# pcb-bldc-drive.net
KiCad netlist of a schematic drawn in EAGLE
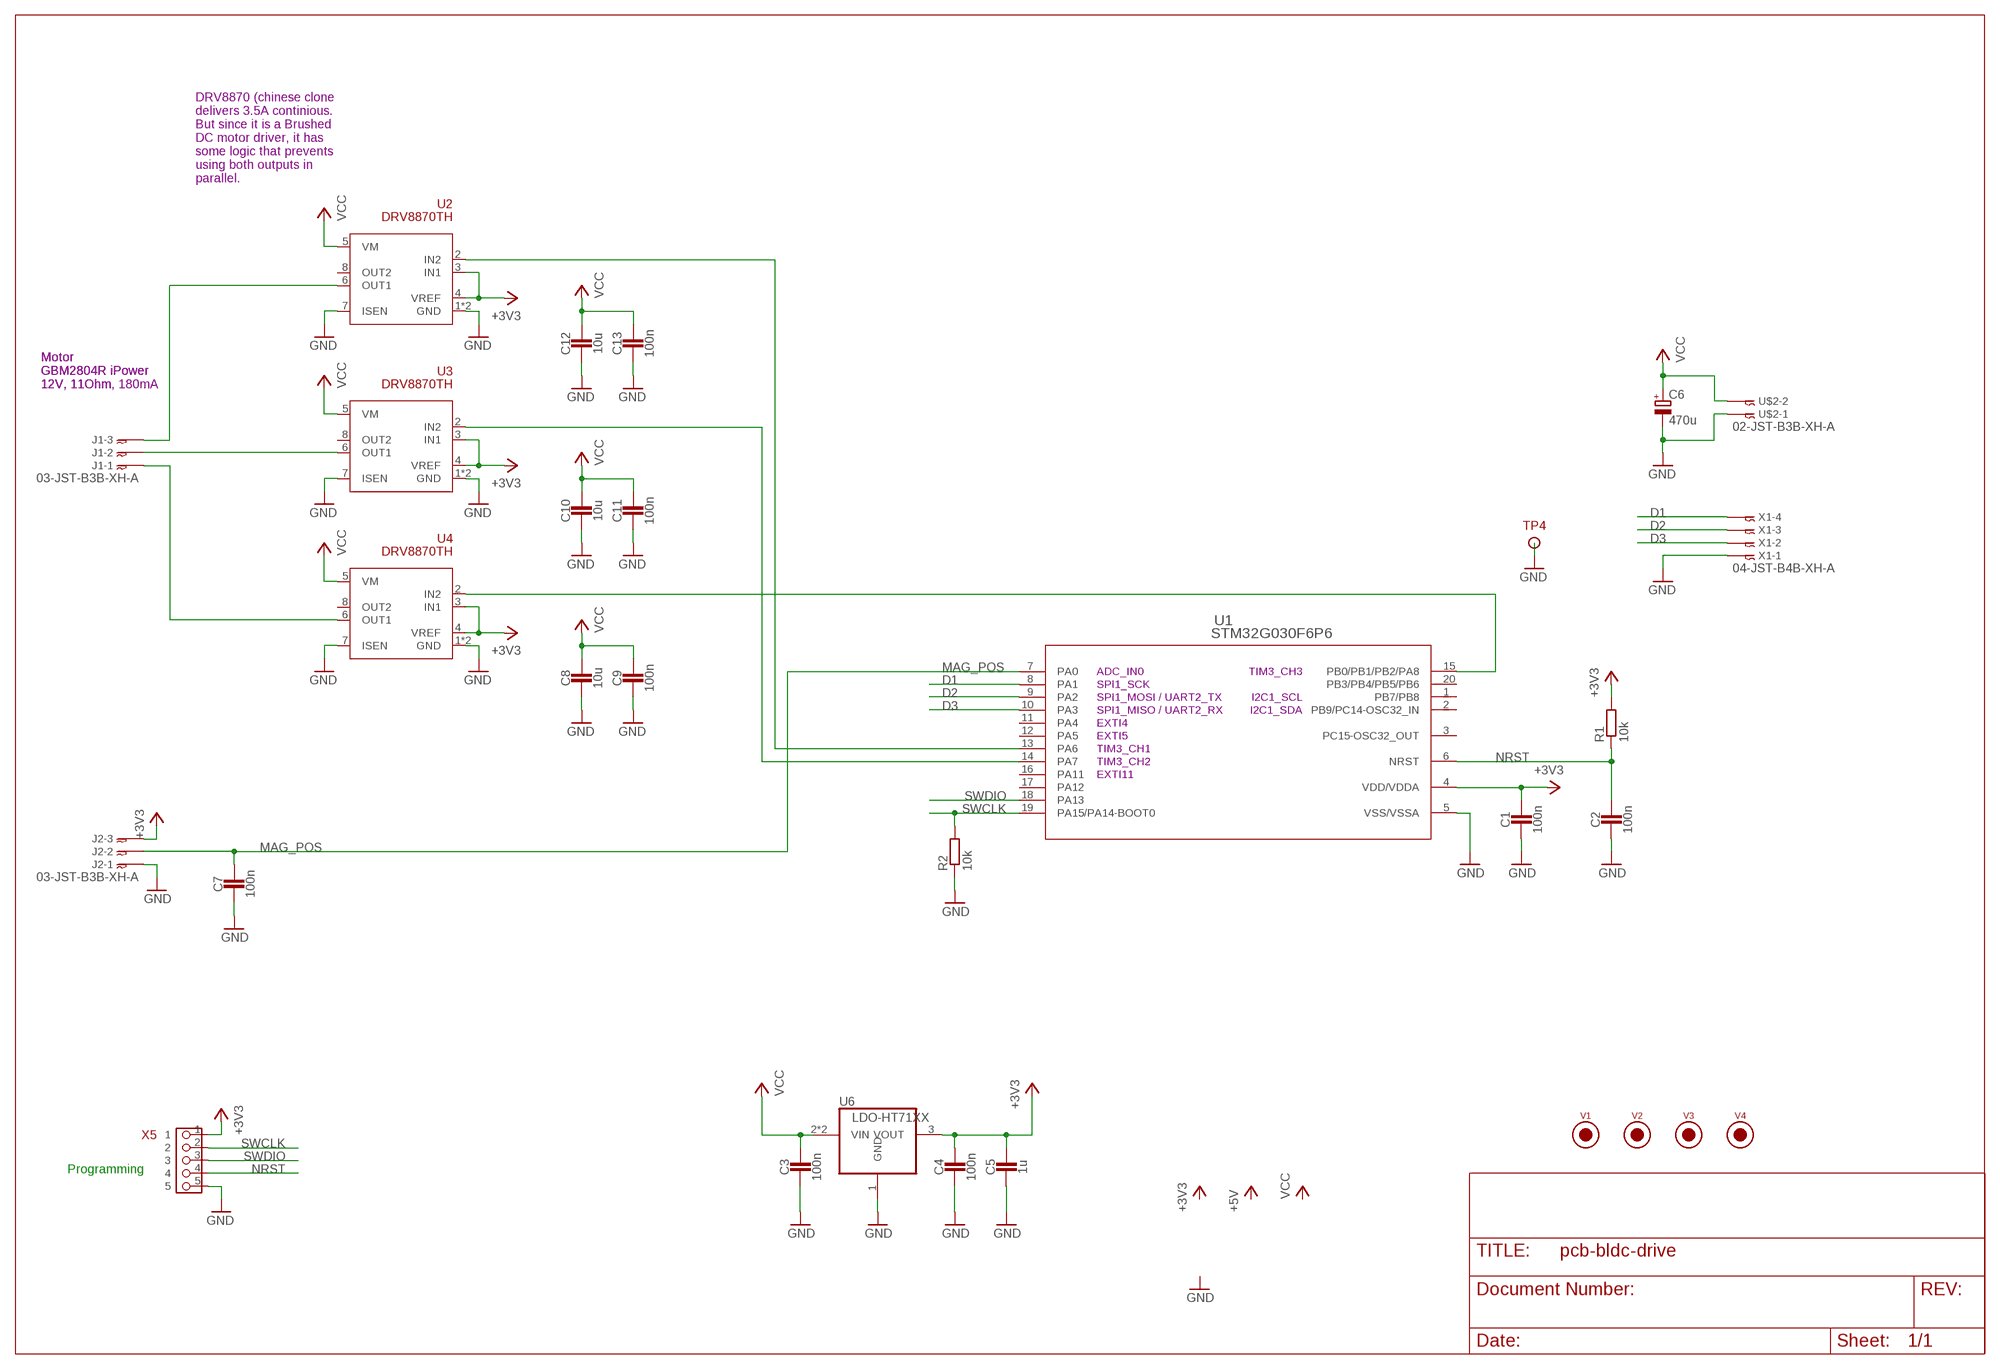
[diagram p0: schematic, sheet 1]

(export (version "E")
  (design (tool "Eeschema 10.0.6"))
  (components
    (comp (ref "C1")
      (value "100n")
      (footprint "eagle-import:0603_CAP")
      (libsource (lib "eagle-import") (part "CAPACITOR0603_CAP"))
    )
    (comp (ref "C2")
      (value "100n")
      (footprint "eagle-import:0603_CAP")
      (libsource (lib "eagle-import") (part "CAPACITOR0603_CAP"))
    )
    (comp (ref "C3")
      (value "100n")
      (footprint "eagle-import:0603_CAP")
      (libsource (lib "eagle-import") (part "CAPACITOR0603_CAP"))
    )
    (comp (ref "C4")
      (value "100n")
      (footprint "eagle-import:0603_CAP")
      (libsource (lib "eagle-import") (part "CAPACITOR0603_CAP"))
    )
    (comp (ref "C5")
      (value "1u")
      (footprint "eagle-import:0603_CAP")
      (libsource (lib "eagle-import") (part "CAPACITOR0603_CAP"))
    )
    (comp (ref "C6")
      (value "470u")
      (footprint "eagle-import:153CLV-1010")
      (libsource (lib "eagle-import") (part "CPOL-EU153CLV-1010"))
    )
    (comp (ref "C7")
      (value "100n")
      (footprint "eagle-import:0603_CAP")
      (libsource (lib "eagle-import") (part "CAPACITOR0603_CAP"))
    )
    (comp (ref "C8")
      (value "10u")
      (footprint "eagle-import:1206_CAP")
      (libsource (lib "eagle-import") (part "CAPACITOR1206_CAP"))
    )
    (comp (ref "C9")
      (value "100n")
      (footprint "eagle-import:0603_CAP")
      (libsource (lib "eagle-import") (part "CAPACITOR0603_CAP"))
    )
    (comp (ref "C10")
      (value "10u")
      (footprint "eagle-import:1206_CAP")
      (libsource (lib "eagle-import") (part "CAPACITOR1206_CAP"))
    )
    (comp (ref "C11")
      (value "100n")
      (footprint "eagle-import:0603_CAP")
      (libsource (lib "eagle-import") (part "CAPACITOR0603_CAP"))
    )
    (comp (ref "C12")
      (value "10u")
      (footprint "eagle-import:1206_CAP")
      (libsource (lib "eagle-import") (part "CAPACITOR1206_CAP"))
    )
    (comp (ref "C13")
      (value "100n")
      (footprint "eagle-import:0603_CAP")
      (libsource (lib "eagle-import") (part "CAPACITOR0603_CAP"))
    )
    (comp (ref "J1")
      (value "03-JST-B3B-XH-A")
      (footprint "eagle-import:B3B-XH")
      (libsource (lib "eagle-import") (part "03-JST-B3B-XH-A"))
    )
    (comp (ref "J2")
      (value "03-JST-B3B-XH-A")
      (footprint "eagle-import:B3B-XH")
      (libsource (lib "eagle-import") (part "03-JST-B3B-XH-A"))
    )
    (comp (ref "R1")
      (value "10k")
      (footprint "eagle-import:0603-RES")
      (libsource (lib "eagle-import") (part "RESISTOR0603_RES"))
    )
    (comp (ref "R2")
      (value "10k")
      (footprint "eagle-import:0603-RES")
      (libsource (lib "eagle-import") (part "RESISTOR0603_RES"))
    )
    (comp (ref "TP4")
      (value "TESTPIN1MM")
      (footprint "eagle-import:PIN-SMD-1X1-TEST_1M0")
      (libsource (lib "eagle-import") (part "TESTPIN1MM"))
    )
    (comp (ref "U$2")
      (value "02-JST-B3B-XH-A")
      (footprint "eagle-import:B2B-XH")
      (libsource (lib "eagle-import") (part "02-JST-B3B-XH-A"))
    )
    (comp (ref "U1")
      (value "STM32G030F6P6")
      (footprint "eagle-import:TSSOP20")
      (fields (field (name "COPYRIGHT") "Copyright (C) 2024 Ultra Librarian. All rights reserved."))
      (libsource (lib "eagle-import") (part "STM32G030F6P6"))
    )
    (comp (ref "U2")
      (value "DRV8870TH")
      (footprint "eagle-import:SOIC-8-THERM")
      (libsource (lib "eagle-import") (part "DRV8870TH"))
    )
    (comp (ref "U3")
      (value "DRV8870TH")
      (footprint "eagle-import:SOIC-8-THERM")
      (libsource (lib "eagle-import") (part "DRV8870TH"))
    )
    (comp (ref "U4")
      (value "DRV8870TH")
      (footprint "eagle-import:SOIC-8-THERM")
      (libsource (lib "eagle-import") (part "DRV8870TH"))
    )
    (comp (ref "U6")
      (value "LDO-HT71XX")
      (footprint "eagle-import:SOT-89")
      (libsource (lib "eagle-import") (part "LDO-HT71XX"))
    )
    (comp (ref "V1")
      (value "FIDUCIAL2MM")
      (footprint "eagle-import:FIDUCIAL_2MM")
      (libsource (lib "eagle-import") (part "FIDUCIAL2MM"))
    )
    (comp (ref "V2")
      (value "FIDUCIAL2MM")
      (footprint "eagle-import:FIDUCIAL_2MM")
      (libsource (lib "eagle-import") (part "FIDUCIAL2MM"))
    )
    (comp (ref "V3")
      (value "FIDUCIAL2MM")
      (footprint "eagle-import:FIDUCIAL_2MM")
      (libsource (lib "eagle-import") (part "FIDUCIAL2MM"))
    )
    (comp (ref "V4")
      (value "FIDUCIAL2MM")
      (footprint "eagle-import:FIDUCIAL_2MM")
      (libsource (lib "eagle-import") (part "FIDUCIAL2MM"))
    )
    (comp (ref "X1")
      (value "04-JST-B4B-XH-A")
      (footprint "eagle-import:B4B-XH")
      (libsource (lib "eagle-import") (part "04-JST-B4B-XH-A"))
    )
    (comp (ref "X5")
      (value "PIN_5X1HD")
      (footprint "eagle-import:PIN_5X1_HD")
      (libsource (lib "eagle-import") (part "PIN_5X1HD"))
    )
  )
  (nets
    (net (code "1") (name "+3V3") (class "Default")
      (node (ref "C1") (pin "1") (pinfunction "1_1") (pintype "bidirectional"))
      (node (ref "C4") (pin "1") (pinfunction "1_1") (pintype "bidirectional"))
      (node (ref "C5") (pin "1") (pinfunction "1_1") (pintype "bidirectional"))
      (node (ref "J2") (pin "P$3") (pinfunction "1_P$3") (pintype "passive"))
      (node (ref "R1") (pin "2") (pinfunction "2_2") (pintype "passive"))
      (node (ref "U1") (pin "4") (pinfunction "VDD/VDDA_4") (pintype "power_in"))
      (node (ref "U2") (pin "3") (pinfunction "IN1_3") (pintype "bidirectional"))
      (node (ref "U2") (pin "4") (pinfunction "VREF_4") (pintype "bidirectional"))
      (node (ref "U3") (pin "3") (pinfunction "IN1_3") (pintype "bidirectional"))
      (node (ref "U3") (pin "4") (pinfunction "VREF_4") (pintype "bidirectional"))
      (node (ref "U4") (pin "3") (pinfunction "IN1_3") (pintype "bidirectional"))
      (node (ref "U4") (pin "4") (pinfunction "VREF_4") (pintype "bidirectional"))
      (node (ref "U6") (pin "3") (pinfunction "VOUT_3") (pintype "output"))
      (node (ref "X5") (pin "1") (pinfunction "1_1") (pintype "bidirectional"))
    )
    (net (code "3") (name "/D1") (class "Default")
      (node (ref "U1") (pin "8") (pinfunction "PA1_8") (pintype "bidirectional"))
      (node (ref "X1") (pin "P$4") (pinfunction "1_P$4") (pintype "passive"))
    )
    (net (code "4") (name "/D2") (class "Default")
      (node (ref "U1") (pin "9") (pinfunction "PA2_9") (pintype "bidirectional"))
      (node (ref "X1") (pin "P$3") (pinfunction "1_P$3") (pintype "passive"))
    )
    (net (code "5") (name "/D3") (class "Default")
      (node (ref "U1") (pin "10") (pinfunction "PA3_10") (pintype "bidirectional"))
      (node (ref "X1") (pin "P$2") (pinfunction "1_P$2") (pintype "passive"))
    )
    (net (code "6") (name "/MAG_POS") (class "Default")
      (node (ref "C7") (pin "1") (pinfunction "1_1") (pintype "bidirectional"))
      (node (ref "J2") (pin "P$2") (pinfunction "1_P$2") (pintype "passive"))
      (node (ref "U1") (pin "7") (pinfunction "PA0_7") (pintype "bidirectional"))
    )
    (net (code "7") (name "/NRST") (class "Default")
      (node (ref "C2") (pin "1") (pinfunction "1_1") (pintype "bidirectional"))
      (node (ref "R1") (pin "1") (pinfunction "1_1") (pintype "passive"))
      (node (ref "U1") (pin "6") (pinfunction "NRST_6") (pintype "bidirectional"))
      (node (ref "X5") (pin "4") (pinfunction "4_4") (pintype "bidirectional"))
    )
    (net (code "8") (name "/SWCLK") (class "Default")
      (node (ref "R2") (pin "2") (pinfunction "2_2") (pintype "passive"))
      (node (ref "U1") (pin "19") (pinfunction "PA15/PA14-BOOT0_19") (pintype "bidirectional"))
      (node (ref "X5") (pin "2") (pinfunction "2_2") (pintype "bidirectional"))
    )
    (net (code "9") (name "/SWDIO") (class "Default")
      (node (ref "U1") (pin "18") (pinfunction "PA13_18") (pintype "bidirectional"))
      (node (ref "X5") (pin "3") (pinfunction "3_3") (pintype "bidirectional"))
    )
    (net (code "10") (name "GND") (class "Default")
      (node (ref "C1") (pin "2") (pinfunction "2_2") (pintype "bidirectional"))
      (node (ref "C10") (pin "2") (pinfunction "2_2") (pintype "bidirectional"))
      (node (ref "C11") (pin "2") (pinfunction "2_2") (pintype "bidirectional"))
      (node (ref "C12") (pin "2") (pinfunction "2_2") (pintype "bidirectional"))
      (node (ref "C13") (pin "2") (pinfunction "2_2") (pintype "bidirectional"))
      (node (ref "C2") (pin "2") (pinfunction "2_2") (pintype "bidirectional"))
      (node (ref "C3") (pin "2") (pinfunction "2_2") (pintype "bidirectional"))
      (node (ref "C4") (pin "2") (pinfunction "2_2") (pintype "bidirectional"))
      (node (ref "C5") (pin "2") (pinfunction "2_2") (pintype "bidirectional"))
      (node (ref "C6") (pin "-") (pinfunction "-_-") (pintype "passive"))
      (node (ref "C7") (pin "2") (pinfunction "2_2") (pintype "bidirectional"))
      (node (ref "C8") (pin "2") (pinfunction "2_2") (pintype "bidirectional"))
      (node (ref "C9") (pin "2") (pinfunction "2_2") (pintype "bidirectional"))
      (node (ref "J2") (pin "P$1") (pinfunction "1_P$1") (pintype "passive"))
      (node (ref "R2") (pin "1") (pinfunction "1_1") (pintype "passive"))
      (node (ref "TP4") (pin "1") (pinfunction "1_1") (pintype "bidirectional"))
      (node (ref "U$2") (pin "P$1") (pinfunction "1_P$1") (pintype "passive"))
      (node (ref "U1") (pin "5") (pinfunction "VSS/VSSA_5") (pintype "power_in"))
      (node (ref "U2") (pin "1") (pinfunction "GND_1") (pintype "bidirectional"))
      (node (ref "U2") (pin "7") (pinfunction "ISEN_7") (pintype "bidirectional"))
      (node (ref "U2") (pin "9") (pinfunction "GND_9") (pintype "bidirectional"))
      (node (ref "U3") (pin "1") (pinfunction "GND_1") (pintype "bidirectional"))
      (node (ref "U3") (pin "7") (pinfunction "ISEN_7") (pintype "bidirectional"))
      (node (ref "U3") (pin "9") (pinfunction "GND_9") (pintype "bidirectional"))
      (node (ref "U4") (pin "1") (pinfunction "GND_1") (pintype "bidirectional"))
      (node (ref "U4") (pin "7") (pinfunction "ISEN_7") (pintype "bidirectional"))
      (node (ref "U4") (pin "9") (pinfunction "GND_9") (pintype "bidirectional"))
      (node (ref "U6") (pin "1") (pinfunction "GND_1") (pintype "power_in"))
      (node (ref "X1") (pin "P$1") (pinfunction "1_P$1") (pintype "passive"))
      (node (ref "X5") (pin "5") (pinfunction "5_5") (pintype "bidirectional"))
    )
    (net (code "11") (name "Net-(J1A-1)") (class "Default")
      (node (ref "J1") (pin "P$1") (pinfunction "1_P$1") (pintype "passive"))
      (node (ref "U4") (pin "6") (pinfunction "OUT1_6") (pintype "bidirectional"))
    )
    (net (code "12") (name "Net-(J1B-1)") (class "Default")
      (node (ref "J1") (pin "P$2") (pinfunction "1_P$2") (pintype "passive"))
      (node (ref "U3") (pin "6") (pinfunction "OUT1_6") (pintype "bidirectional"))
    )
    (net (code "13") (name "Net-(J1C-1)") (class "Default")
      (node (ref "J1") (pin "P$3") (pinfunction "1_P$3") (pintype "passive"))
      (node (ref "U2") (pin "6") (pinfunction "OUT1_6") (pintype "bidirectional"))
    )
    (net (code "14") (name "Net-(U1-PA6)") (class "Default")
      (node (ref "U1") (pin "13") (pinfunction "PA6_13") (pintype "bidirectional"))
      (node (ref "U2") (pin "2") (pinfunction "IN2_2") (pintype "bidirectional"))
    )
    (net (code "15") (name "Net-(U1-PA7)") (class "Default")
      (node (ref "U1") (pin "14") (pinfunction "PA7_14") (pintype "bidirectional"))
      (node (ref "U3") (pin "2") (pinfunction "IN2_2") (pintype "bidirectional"))
    )
    (net (code "16") (name "Net-(U1-PB0{slash}PB1{slash}PB2{slash}PA8)") (class "Default")
      (node (ref "U1") (pin "15") (pinfunction "PB0/PB1/PB2/PA8_15") (pintype "bidirectional"))
      (node (ref "U4") (pin "2") (pinfunction "IN2_2") (pintype "bidirectional"))
    )
    (net (code "17") (name "VCC") (class "Default")
      (node (ref "C10") (pin "1") (pinfunction "1_1") (pintype "bidirectional"))
      (node (ref "C11") (pin "1") (pinfunction "1_1") (pintype "bidirectional"))
      (node (ref "C12") (pin "1") (pinfunction "1_1") (pintype "bidirectional"))
      (node (ref "C13") (pin "1") (pinfunction "1_1") (pintype "bidirectional"))
      (node (ref "C3") (pin "1") (pinfunction "1_1") (pintype "bidirectional"))
      (node (ref "C6") (pin "+") (pinfunction "+_+") (pintype "passive"))
      (node (ref "C8") (pin "1") (pinfunction "1_1") (pintype "bidirectional"))
      (node (ref "C9") (pin "1") (pinfunction "1_1") (pintype "bidirectional"))
      (node (ref "U$2") (pin "P$2") (pinfunction "1_P$2") (pintype "passive"))
      (node (ref "U2") (pin "5") (pinfunction "VM_5") (pintype "bidirectional"))
      (node (ref "U3") (pin "5") (pinfunction "VM_5") (pintype "bidirectional"))
      (node (ref "U4") (pin "5") (pinfunction "VM_5") (pintype "bidirectional"))
      (node (ref "U6") (pin "2") (pinfunction "VIN_2") (pintype "input"))
      (node (ref "U6") (pin "2@1") (pinfunction "VIN_2@1") (pintype "input"))
    )
    (net (code "18") (name "unconnected-(U1-PA4-Pad11)") (class "Default")
      (node (ref "U1") (pin "11") (pinfunction "PA4_11") (pintype "bidirectional"))
    )
    (net (code "19") (name "unconnected-(U1-PA5-Pad12)") (class "Default")
      (node (ref "U1") (pin "12") (pinfunction "PA5_12") (pintype "bidirectional"))
    )
    (net (code "20") (name "unconnected-(U1-PA11-Pad16)") (class "Default")
      (node (ref "U1") (pin "16") (pinfunction "PA11_16") (pintype "bidirectional"))
    )
    (net (code "21") (name "unconnected-(U1-PA12-Pad17)") (class "Default")
      (node (ref "U1") (pin "17") (pinfunction "PA12_17") (pintype "bidirectional"))
    )
    (net (code "22") (name "unconnected-(U1-PB3{slash}PB4{slash}PB5{slash}PB6-Pad20)") (class "Default")
      (node (ref "U1") (pin "20") (pinfunction "PB3/PB4/PB5/PB6_20") (pintype "bidirectional"))
    )
    (net (code "23") (name "unconnected-(U1-PB7{slash}PB8-Pad1)") (class "Default")
      (node (ref "U1") (pin "1") (pinfunction "PB7/PB8_1") (pintype "bidirectional"))
    )
    (net (code "24") (name "unconnected-(U1-PB9{slash}PC14-OSC32_IN-Pad2)") (class "Default")
      (node (ref "U1") (pin "2") (pinfunction "PB9/PC14-OSC32_IN_2") (pintype "bidirectional"))
    )
    (net (code "25") (name "unconnected-(U1-PC15-OSC32_OUT-Pad3)") (class "Default")
      (node (ref "U1") (pin "3") (pinfunction "PC15-OSC32_OUT_3") (pintype "bidirectional"))
    )
    (net (code "26") (name "unconnected-(U2-OUT2-Pad8)") (class "Default")
      (node (ref "U2") (pin "8") (pinfunction "OUT2_8") (pintype "bidirectional"))
    )
    (net (code "27") (name "unconnected-(U3-OUT2-Pad8)") (class "Default")
      (node (ref "U3") (pin "8") (pinfunction "OUT2_8") (pintype "bidirectional"))
    )
    (net (code "28") (name "unconnected-(U4-OUT2-Pad8)") (class "Default")
      (node (ref "U4") (pin "8") (pinfunction "OUT2_8") (pintype "bidirectional"))
    )
  )
)
